# 1_V1.net
KiCad netlist of a schematic drawn in Altium Designer
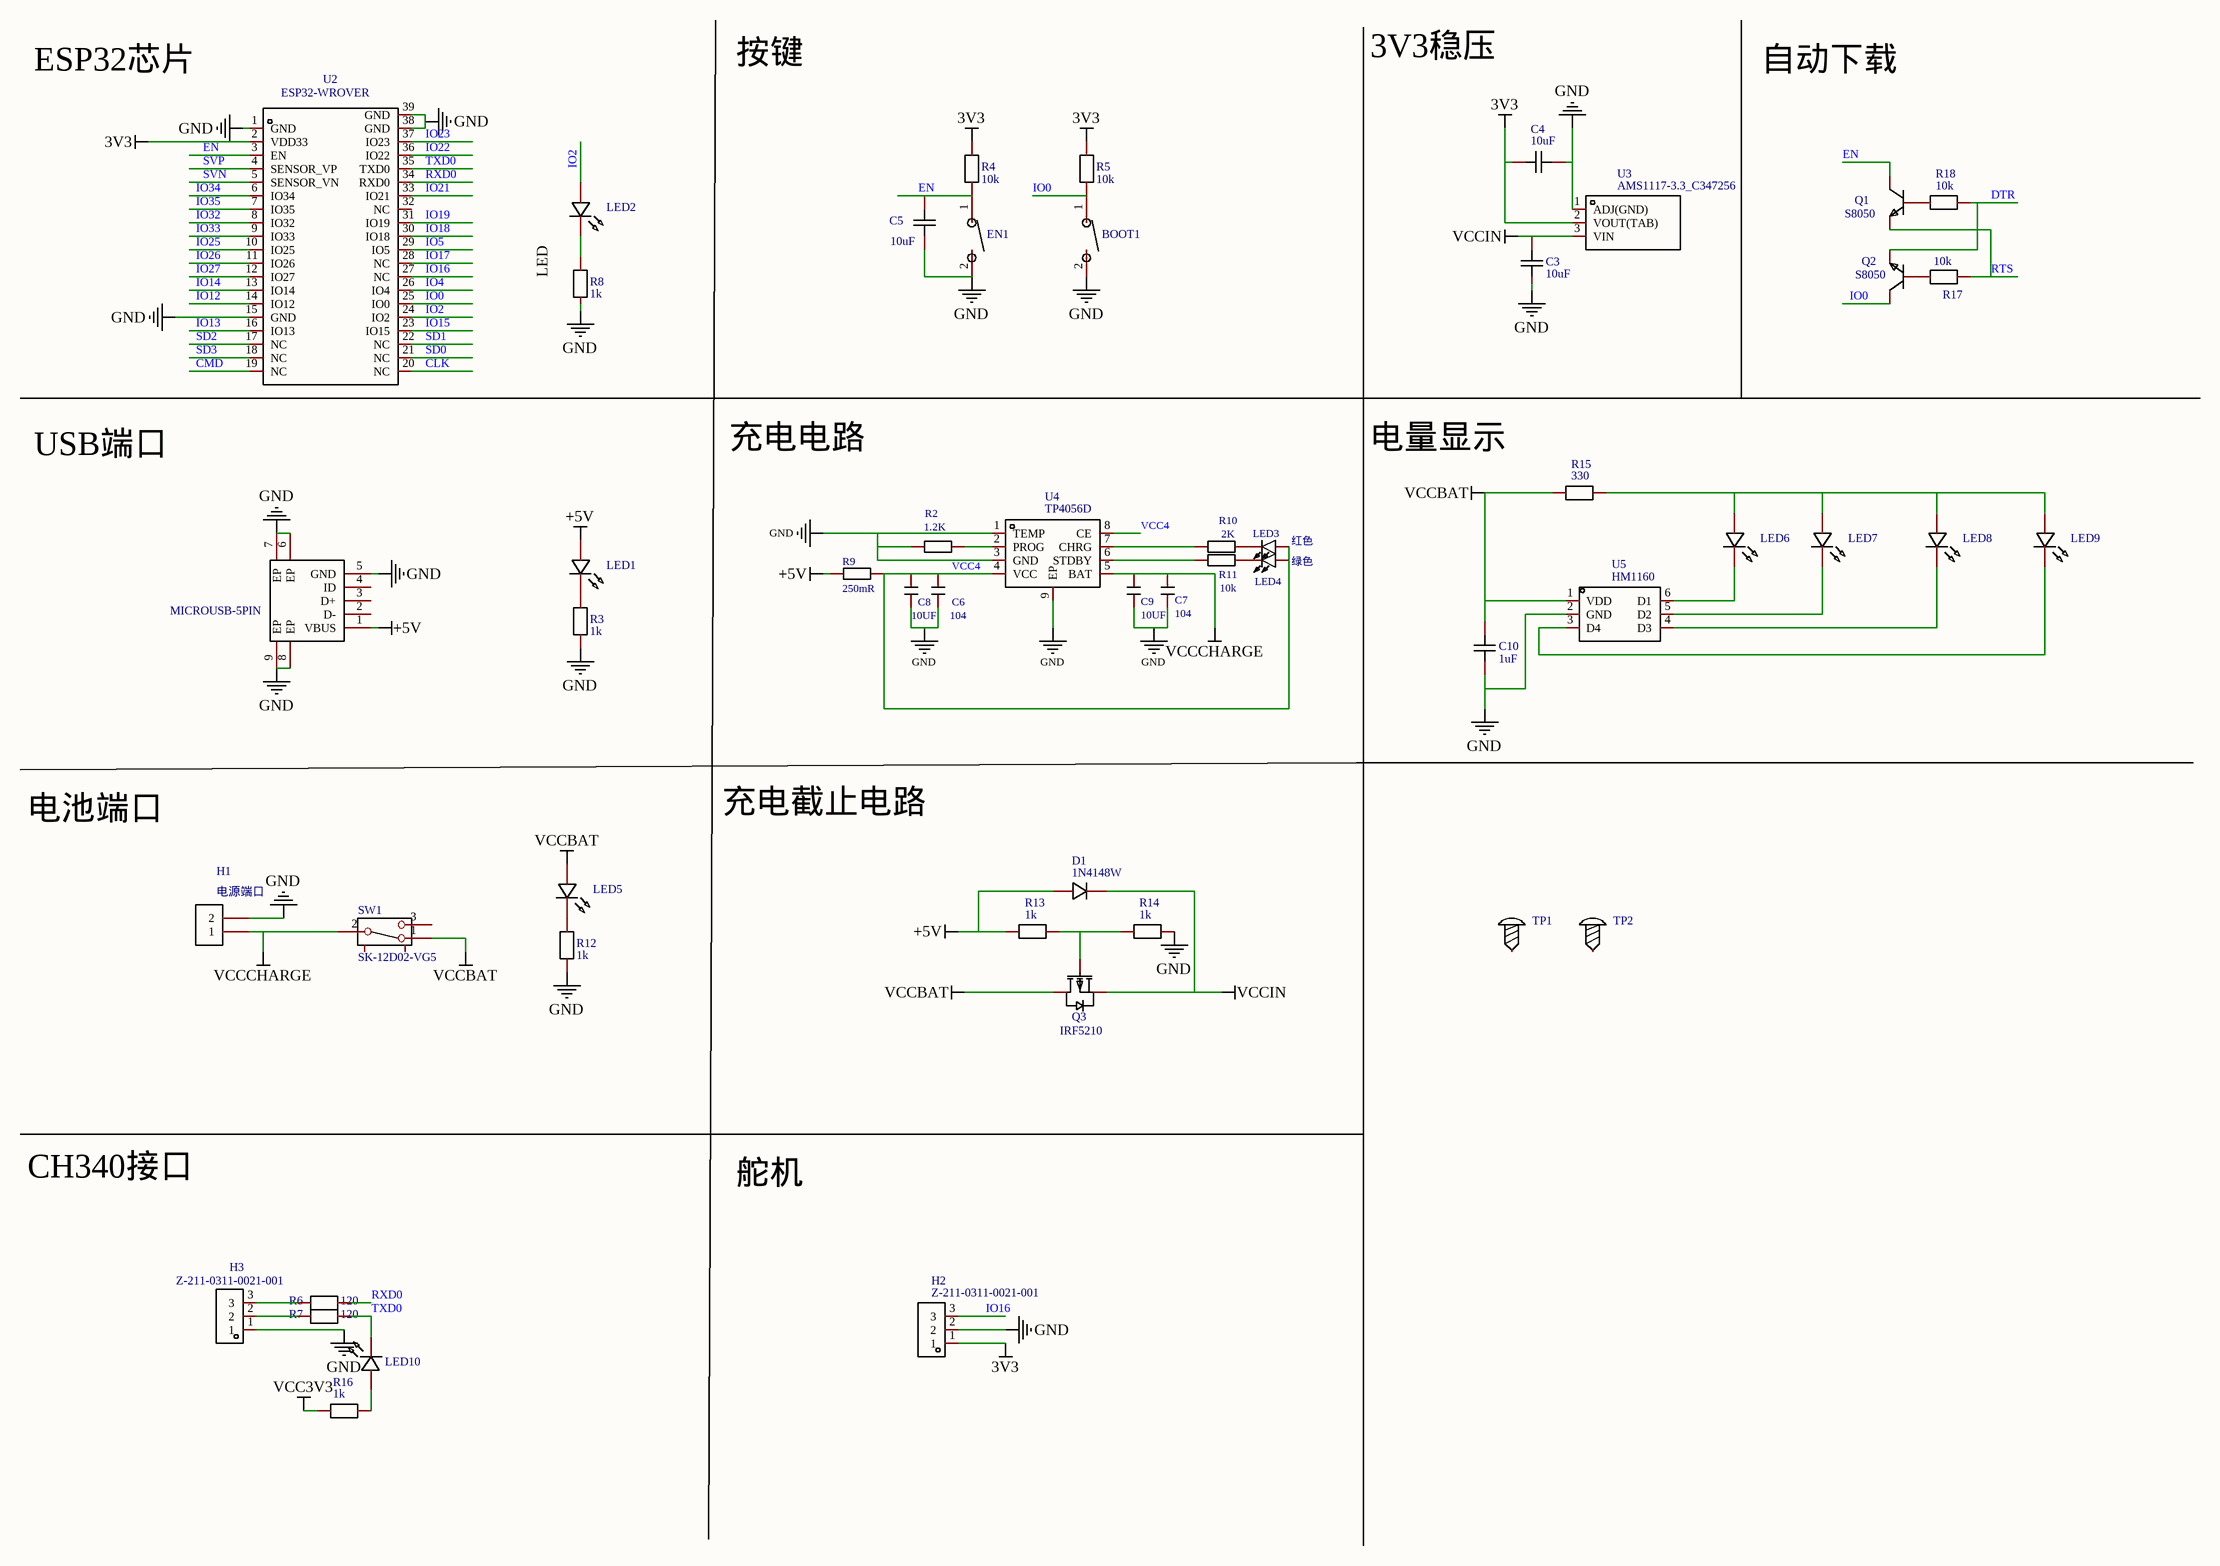
[diagram p0: 1_V1.schdoc]

(export (version "E")
  (design (tool "Eeschema 10.0.6"))
  (components
    (comp (ref "BOOT1")
      (value "TSA343G00D-250J2")
      (description "触点电流:50mA;额定电压(DC):12V;电路结构:单刀单掷;按钮作用方向:顶部触动;致动器样式:圆形按钮;照明颜色:-;开关长度:4mm;开关宽度:3mm;开关高度:2mm;")
      (fields (field (name "MANUFACTURER") "BRIGHT(博瑞泰)"))
      (libsource (lib "altium-import") (part "root_3_TSA343G00D-250J2_"))
    )
    (comp (ref "C3")
      (value "10uF")
      (fields (field (name "NAME") "10uF"))
      (libsource (lib "altium-import") (part "root_3_10uF_"))
    )
    (comp (ref "C4")
      (value "10uF")
      (fields (field (name "NAME") "10uF"))
      (libsource (lib "altium-import") (part "root_0_10uF_"))
    )
    (comp (ref "C5")
      (value "10uF")
      (fields (field (name "NAME") "10uF"))
      (libsource (lib "altium-import") (part "root_1_10uF_"))
    )
    (comp (ref "C6")
      (value "104")
      (fields (field (name "NAME") "104") (field (name "版权归属") "源创客"))
      (libsource (lib "altium-import") (part "root_1_104_"))
    )
    (comp (ref "C7")
      (value "104")
      (fields (field (name "NAME") "104") (field (name "版权归属") "源创客"))
      (libsource (lib "altium-import") (part "root_1_104_"))
    )
    (comp (ref "C8")
      (value "10UF")
      (fields (field (name "NAME") "10UF") (field (name "版权归属") "源创客"))
      (libsource (lib "altium-import") (part "root_1_10UF_"))
    )
    (comp (ref "C9")
      (value "10UF")
      (fields (field (name "NAME") "10UF") (field (name "版权归属") "源创客"))
      (libsource (lib "altium-import") (part "root_1_10UF_"))
    )
    (comp (ref "C10")
      (value "1uF")
      (fields (field (name "NAME") "1uF"))
      (libsource (lib "altium-import") (part "root_1_1uF_"))
    )
    (comp (ref "D1")
      (value "1N4148W")
      (fields (field (name "NAME") "1N4148W") (field (name "MANUFACTURER") "Tak Cheong"))
      (libsource (lib "altium-import") (part "root_0_1N4148W_"))
    )
    (comp (ref "EN1")
      (value "TSA343G00D-250J2")
      (description "触点电流:50mA;额定电压(DC):12V;电路结构:单刀单掷;按钮作用方向:顶部触动;致动器样式:圆形按钮;照明颜色:-;开关长度:4mm;开关宽度:3mm;开关高度:2mm;")
      (fields (field (name "MANUFACTURER") "BRIGHT(博瑞泰)"))
      (libsource (lib "altium-import") (part "root_3_TSA343G00D-250J2_"))
    )
    (comp (ref "H1")
      (value "电源端口")
      (fields
        (field (name "NAME") "电源端口")
        (field (name "MANUFACTURER") "TE Connectivity(美国泰科)")
        (field (name "MANUFACTURER PART") "3-644456-2")
      )
      (libsource (lib "altium-import") (part "root_2_电源端口_"))
    )
    (comp (ref "H2")
      (value "Z-211-0311-0021-001")
      (fields (field (name "NAME") "Z-211-0311-0021-001") (field (name "MANUFACTURER") "Nextron(正凌)"))
      (libsource (lib "altium-import") (part "root_2_Z-211-0311-0021-001_"))
    )
    (comp (ref "H3")
      (value "Z-211-0311-0021-001")
      (fields (field (name "NAME") "Z-211-0311-0021-001") (field (name "MANUFACTURER") "Nextron(正凌)"))
      (libsource (lib "altium-import") (part "root_2_Z-211-0311-0021-001_"))
    )
    (comp (ref "LED1")
      (value "LED-0603_R")
      (fields
        (field (name "MANUFACTURER") "EVERLIGHT(台湾亿光)")
        (field (name "MANUFACTURER PART") "19-217/R6C-AL1M2VY/3T")
      )
      (libsource (lib "altium-import") (part "root_3_LED-0603_R_"))
    )
    (comp (ref "LED2")
      (value "LED-0603_R")
      (fields
        (field (name "MANUFACTURER") "EVERLIGHT(台湾亿光)")
        (field (name "MANUFACTURER PART") "19-217/R6C-AL1M2VY/3T")
      )
      (libsource (lib "altium-import") (part "root_3_LED-0603_R_"))
    )
    (comp (ref "LED3")
      (value "红色")
      (fields (field (name "NAME") "红色") (field (name "版权归属") "源创客"))
      (libsource (lib "altium-import") (part "root_3_红色_"))
    )
    (comp (ref "LED4")
      (value "绿色")
      (fields (field (name "NAME") "绿色") (field (name "版权归属") "源创客"))
      (libsource (lib "altium-import") (part "root_3_绿色_"))
    )
    (comp (ref "LED5")
      (value "LED-0603_R")
      (fields
        (field (name "MANUFACTURER") "EVERLIGHT(台湾亿光)")
        (field (name "MANUFACTURER PART") "19-217/R6C-AL1M2VY/3T")
      )
      (libsource (lib "altium-import") (part "root_3_LED-0603_R_"))
    )
    (comp (ref "LED6")
      (value "LED-0603_R")
      (fields
        (field (name "MANUFACTURER") "EVERLIGHT(台湾亿光)")
        (field (name "MANUFACTURER PART") "19-217/R6C-AL1M2VY/3T")
      )
      (libsource (lib "altium-import") (part "root_3_LED-0603_R_"))
    )
    (comp (ref "LED7")
      (value "LED-0603_R")
      (fields
        (field (name "MANUFACTURER") "EVERLIGHT(台湾亿光)")
        (field (name "MANUFACTURER PART") "19-217/R6C-AL1M2VY/3T")
      )
      (libsource (lib "altium-import") (part "root_3_LED-0603_R_"))
    )
    (comp (ref "LED8")
      (value "LED-0603_R")
      (fields
        (field (name "MANUFACTURER") "EVERLIGHT(台湾亿光)")
        (field (name "MANUFACTURER PART") "19-217/R6C-AL1M2VY/3T")
      )
      (libsource (lib "altium-import") (part "root_3_LED-0603_R_"))
    )
    (comp (ref "LED9")
      (value "LED-0603_R")
      (fields
        (field (name "MANUFACTURER") "EVERLIGHT(台湾亿光)")
        (field (name "MANUFACTURER PART") "19-217/R6C-AL1M2VY/3T")
      )
      (libsource (lib "altium-import") (part "root_3_LED-0603_R_"))
    )
    (comp (ref "LED10")
      (value "LED-0603_R")
      (fields
        (field (name "MANUFACTURER") "EVERLIGHT(台湾亿光)")
        (field (name "MANUFACTURER PART") "19-217/R6C-AL1M2VY/3T")
      )
      (libsource (lib "altium-import") (part "root_1_LED-0603_R_"))
    )
    (comp (ref "NO1")
      (value "MICROUSB-5PIN")
      (fields (field (name "NAME") "MICROUSB-5PIN") (field (name "MANUFACTURER PART") "MicroUSB-5PIN"))
      (libsource (lib "altium-import") (part "root_2_MICROUSB-5PIN_"))
    )
    (comp (ref "Q1")
      (value "S8050")
      (fields (field (name "NAME") "S8050") (field (name "MANUFACTURER") "WPMtek(维攀微)"))
      (libsource (lib "altium-import") (part "root_0_S8050_"))
    )
    (comp (ref "Q2")
      (value "S8050")
      (fields (field (name "NAME") "S8050") (field (name "MANUFACTURER") "WPMtek(维攀微)"))
      (libsource (lib "altium-import") (part "root_2_S8050_"))
    )
    (comp (ref "Q3")
      (value "IRF5210")
      (fields
        (field (name "NAME") "IRF5210")
        (field (name "MANUFACTURER") "IR")
        (field (name "MANUFACTURER PART") "IRF5210STRLPBF")
      )
      (libsource (lib "altium-import") (part "root_3_IRF5210_"))
    )
    (comp (ref "R2")
      (value "1.2K")
      (fields (field (name "NAME") "1.2K") (field (name "版权归属") "源创客"))
      (libsource (lib "altium-import") (part "root_0_1K_"))
    )
    (comp (ref "R3")
      (value "1k")
      (fields (field (name "NAME") "1k"))
      (libsource (lib "altium-import") (part "root_3_1k_"))
    )
    (comp (ref "R4")
      (value "10k")
      (fields (field (name "NAME") "10k"))
      (libsource (lib "altium-import") (part "root_1_10k_"))
    )
    (comp (ref "R5")
      (value "10k")
      (fields (field (name "NAME") "10k"))
      (libsource (lib "altium-import") (part "root_1_10k_"))
    )
    (comp (ref "R6")
      (value "120")
      (fields (field (name "NAME") "120"))
      (libsource (lib "altium-import") (part "root_0_120_"))
    )
    (comp (ref "R7")
      (value "120")
      (fields (field (name "NAME") "120"))
      (libsource (lib "altium-import") (part "root_0_120_"))
    )
    (comp (ref "R8")
      (value "1k")
      (fields (field (name "NAME") "1k"))
      (libsource (lib "altium-import") (part "root_3_1k_"))
    )
    (comp (ref "R9")
      (value "250mR")
      (fields (field (name "NAME") "250mR") (field (name "版权归属") "源创客"))
      (libsource (lib "altium-import") (part "root_0_250mR_"))
    )
    (comp (ref "R10")
      (value "2K")
      (fields (field (name "NAME") "2K") (field (name "版权归属") "源创客"))
      (libsource (lib "altium-import") (part "root_0_2K_"))
    )
    (comp (ref "R11")
      (value "10k")
      (fields (field (name "NAME") "10k") (field (name "版权归属") "源创客"))
      (libsource (lib "") (part "root_0_10k__1"))
    )
    (comp (ref "R12")
      (value "1k")
      (fields (field (name "NAME") "1k"))
      (libsource (lib "altium-import") (part "root_3_1k_"))
    )
    (comp (ref "R13")
      (value "1k")
      (fields (field (name "NAME") "1k"))
      (libsource (lib "altium-import") (part "root_0_1k_"))
    )
    (comp (ref "R14")
      (value "1k")
      (fields (field (name "NAME") "1k"))
      (libsource (lib "altium-import") (part "root_0_1k_"))
    )
    (comp (ref "R15")
      (value "330")
      (fields (field (name "NAME") "330"))
      (libsource (lib "altium-import") (part "root_0_330_"))
    )
    (comp (ref "R16")
      (value "1k")
      (fields (field (name "NAME") "1k"))
      (libsource (lib "altium-import") (part "root_0_1k_"))
    )
    (comp (ref "R17")
      (value "10k")
      (fields (field (name "NAME") "10k"))
      (libsource (lib "altium-import") (part "root_0_10k_"))
    )
    (comp (ref "R18")
      (value "10k")
      (fields (field (name "NAME") "10k"))
      (libsource (lib "altium-import") (part "root_0_10k_"))
    )
    (comp (ref "SW1")
      (value "SK-12D02-VG5")
      (fields (field (name "NAME") "SK-12D02-VG5") (field (name "MANUFACTURER") "韩国韩荣"))
      (libsource (lib "altium-import") (part "root_0_SK-12D02-VG5_C136722_"))
    )
    (comp (ref "TP1") (value "M2螺丝") (libsource (lib "altium-import") (part "root_0_M2螺丝_")))
    (comp (ref "TP2") (value "M2螺丝") (libsource (lib "altium-import") (part "root_0_M2螺丝_")))
    (comp (ref "U2")
      (value "ESP32-WROVER")
      (fields
        (field (name "NAME") "ESP32-WROVER")
        (field (name "MANUFACTURER") "Espressif Systems")
        (field (name "MANUFACTURER PART") "ESP32-WROVER-E(16MB)")
      )
      (libsource (lib "altium-import") (part "root_0_ESP32-WROVER_"))
    )
    (comp (ref "U3")
      (value "AMS1117-3.3_C347256")
      (fields
        (field (name "NAME") "AMS1117-3.3_C347256")
        (field (name "MANUFACTURER") "Youtai Semiconductor Co., Ltd.")
        (field (name "MANUFACTURER PART") "AMS1117-3.3")
      )
      (libsource (lib "altium-import") (part "root_0_AMS1117-3.3_C347256_"))
    )
    (comp (ref "U4")
      (value "TP4056D")
      (fields (field (name "NAME") "TP4056D") (field (name "MANUFACTURER") "拓微集成"))
      (libsource (lib "altium-import") (part "root_0_TP4056D_"))
    )
    (comp (ref "U5")
      (value "HM1160")
      (fields
        (field (name "NAME") "HM1160")
        (field (name "MANUFACTURER") "Shenzhen Chip Hope Micro-Electronics")
        (field (name "MANUFACTURER PART") "LP3772-1")
      )
      (libsource (lib "altium-import") (part "root_0_HM1160_"))
    )
  )
  (nets
    (net (code "1") (name "+5V") (class "Default")
      (node (ref "D1") (pin "2") (pinfunction "2_2") (pintype "passive"))
      (node (ref "LED1") (pin "1") (pinfunction "1_1") (pintype "passive"))
      (node (ref "NO1") (pin "1") (pinfunction "VBUS_1") (pintype "passive"))
      (node (ref "R13") (pin "1") (pinfunction "1_1") (pintype "passive"))
      (node (ref "R9") (pin "1") (pinfunction "1_1") (pintype "passive"))
    )
    (net (code "2") (name "/CLK") (class "Default")
      (node (ref "U2") (pin "20") (pinfunction "NC_20") (pintype "passive"))
    )
    (net (code "3") (name "/CMD") (class "Default")
      (node (ref "U2") (pin "19") (pinfunction "NC_19") (pintype "passive"))
    )
    (net (code "4") (name "/DTR") (class "Default")
      (node (ref "Q2") (pin "2") (pinfunction "E_2") (pintype "passive"))
      (node (ref "R18") (pin "2") (pinfunction "2_2") (pintype "passive"))
    )
    (net (code "5") (name "/EN") (class "Default")
      (node (ref "C5") (pin "2") (pinfunction "2_2") (pintype "passive"))
      (node (ref "EN1") (pin "1") (pinfunction "1_1") (pintype "passive"))
      (node (ref "Q1") (pin "3") (pinfunction "C_3") (pintype "passive"))
      (node (ref "R4") (pin "1") (pinfunction "1_1") (pintype "passive"))
      (node (ref "U2") (pin "3") (pinfunction "EN_3") (pintype "passive"))
    )
    (net (code "6") (name "/IO0") (class "Default")
      (node (ref "BOOT1") (pin "1") (pinfunction "1_1") (pintype "passive"))
      (node (ref "Q2") (pin "3") (pinfunction "C_3") (pintype "passive"))
      (node (ref "R5") (pin "1") (pinfunction "1_1") (pintype "passive"))
      (node (ref "U2") (pin "25") (pinfunction "IO0_25") (pintype "passive"))
    )
    (net (code "7") (name "/IO2") (class "Default")
      (node (ref "LED2") (pin "1") (pinfunction "1_1") (pintype "passive"))
      (node (ref "U2") (pin "24") (pinfunction "IO2_24") (pintype "passive"))
    )
    (net (code "8") (name "/IO4") (class "Default")
      (node (ref "U2") (pin "26") (pinfunction "IO4_26") (pintype "passive"))
    )
    (net (code "9") (name "/IO5") (class "Default")
      (node (ref "U2") (pin "29") (pinfunction "IO5_29") (pintype "passive"))
    )
    (net (code "10") (name "/IO12") (class "Default")
      (node (ref "U2") (pin "14") (pinfunction "IO12_14") (pintype "passive"))
    )
    (net (code "11") (name "/IO13") (class "Default")
      (node (ref "U2") (pin "16") (pinfunction "IO13_16") (pintype "passive"))
    )
    (net (code "12") (name "/IO14") (class "Default")
      (node (ref "U2") (pin "13") (pinfunction "IO14_13") (pintype "passive"))
    )
    (net (code "13") (name "/IO15") (class "Default")
      (node (ref "U2") (pin "23") (pinfunction "IO15_23") (pintype "passive"))
    )
    (net (code "14") (name "/IO16") (class "Default")
      (node (ref "H2") (pin "3") (pinfunction "3_3") (pintype "passive"))
      (node (ref "U2") (pin "27") (pinfunction "NC_27") (pintype "passive"))
    )
    (net (code "15") (name "/IO17") (class "Default")
      (node (ref "U2") (pin "28") (pinfunction "NC_28") (pintype "passive"))
    )
    (net (code "16") (name "/IO18") (class "Default")
      (node (ref "U2") (pin "30") (pinfunction "IO18_30") (pintype "passive"))
    )
    (net (code "17") (name "/IO19") (class "Default")
      (node (ref "U2") (pin "31") (pinfunction "IO19_31") (pintype "passive"))
    )
    (net (code "18") (name "/IO21") (class "Default")
      (node (ref "U2") (pin "33") (pinfunction "IO21_33") (pintype "passive"))
    )
    (net (code "19") (name "/IO22") (class "Default")
      (node (ref "U2") (pin "36") (pinfunction "IO22_36") (pintype "passive"))
    )
    (net (code "20") (name "/IO23") (class "Default")
      (node (ref "U2") (pin "37") (pinfunction "IO23_37") (pintype "passive"))
    )
    (net (code "21") (name "/IO25") (class "Default")
      (node (ref "U2") (pin "10") (pinfunction "IO25_10") (pintype "passive"))
    )
    (net (code "22") (name "/IO26") (class "Default")
      (node (ref "U2") (pin "11") (pinfunction "IO26_11") (pintype "passive"))
    )
    (net (code "23") (name "/IO27") (class "Default")
      (node (ref "U2") (pin "12") (pinfunction "IO27_12") (pintype "passive"))
    )
    (net (code "24") (name "/IO32") (class "Default")
      (node (ref "U2") (pin "8") (pinfunction "IO32_8") (pintype "passive"))
    )
    (net (code "25") (name "/IO33") (class "Default")
      (node (ref "U2") (pin "9") (pinfunction "IO33_9") (pintype "passive"))
    )
    (net (code "26") (name "/IO34") (class "Default")
      (node (ref "U2") (pin "6") (pinfunction "IO34_6") (pintype "passive"))
    )
    (net (code "27") (name "/IO35") (class "Default")
      (node (ref "U2") (pin "7") (pinfunction "IO35_7") (pintype "passive"))
    )
    (net (code "28") (name "/RTS") (class "Default")
      (node (ref "Q1") (pin "2") (pinfunction "E_2") (pintype "passive"))
      (node (ref "R17") (pin "2") (pinfunction "2_2") (pintype "passive"))
    )
    (net (code "29") (name "/RXD0") (class "Default")
      (node (ref "R6") (pin "2") (pinfunction "2_2") (pintype "passive"))
      (node (ref "U2") (pin "34") (pinfunction "RXD0_34") (pintype "passive"))
    )
    (net (code "30") (name "/SD0") (class "Default")
      (node (ref "U2") (pin "21") (pinfunction "NC_21") (pintype "passive"))
    )
    (net (code "31") (name "/SD1") (class "Default")
      (node (ref "U2") (pin "22") (pinfunction "NC_22") (pintype "passive"))
    )
    (net (code "32") (name "/SD2") (class "Default")
      (node (ref "U2") (pin "17") (pinfunction "NC_17") (pintype "passive"))
    )
    (net (code "33") (name "/SD3") (class "Default")
      (node (ref "U2") (pin "18") (pinfunction "NC_18") (pintype "passive"))
    )
    (net (code "34") (name "/SVN") (class "Default")
      (node (ref "U2") (pin "5") (pinfunction "SENSOR_VN_5") (pintype "passive"))
    )
    (net (code "35") (name "/SVP") (class "Default")
      (node (ref "U2") (pin "4") (pinfunction "SENSOR_VP_4") (pintype "passive"))
    )
    (net (code "36") (name "/TXD0") (class "Default")
      (node (ref "LED10") (pin "2") (pinfunction "2_2") (pintype "passive"))
      (node (ref "R7") (pin "2") (pinfunction "2_2") (pintype "passive"))
      (node (ref "U2") (pin "35") (pinfunction "TXD0_35") (pintype "passive"))
    )
    (net (code "37") (name "/VCC4") (class "Default")
      (node (ref "C6") (pin "2") (pinfunction "2_2") (pintype "passive"))
      (node (ref "C8") (pin "2") (pinfunction "2_2") (pintype "passive"))
      (node (ref "LED3") (pin "1") (pinfunction "A_1") (pintype "passive"))
      (node (ref "LED4") (pin "1") (pinfunction "A_1") (pintype "passive"))
      (node (ref "R9") (pin "2") (pinfunction "2_2") (pintype "passive"))
      (node (ref "U4") (pin "4") (pinfunction "VCC_4") (pintype "passive"))
      (node (ref "U4") (pin "8") (pinfunction "CE_8") (pintype "passive"))
    )
    (net (code "38") (name "3V3") (class "Default")
      (node (ref "C4") (pin "1") (pinfunction "1_1") (pintype "passive"))
      (node (ref "H2") (pin "1") (pinfunction "1_1") (pintype "passive"))
      (node (ref "R4") (pin "2") (pinfunction "2_2") (pintype "passive"))
      (node (ref "R5") (pin "2") (pinfunction "2_2") (pintype "passive"))
      (node (ref "U2") (pin "2") (pinfunction "VDD33_2") (pintype "passive"))
      (node (ref "U3") (pin "2") (pinfunction "VOUT(TAB)_2") (pintype "passive"))
    )
    (net (code "39") (name "GND") (class "Default")
      (node (ref "BOOT1") (pin "2") (pinfunction "2_2") (pintype "passive"))
      (node (ref "C10") (pin "1") (pinfunction "1_1") (pintype "passive"))
      (node (ref "C3") (pin "2") (pinfunction "2_2") (pintype "passive"))
      (node (ref "C4") (pin "2") (pinfunction "2_2") (pintype "passive"))
      (node (ref "C5") (pin "1") (pinfunction "1_1") (pintype "passive"))
      (node (ref "C6") (pin "1") (pinfunction "1_1") (pintype "passive"))
      (node (ref "C7") (pin "1") (pinfunction "1_1") (pintype "passive"))
      (node (ref "C8") (pin "1") (pinfunction "1_1") (pintype "passive"))
      (node (ref "C9") (pin "1") (pinfunction "1_1") (pintype "passive"))
      (node (ref "EN1") (pin "2") (pinfunction "2_2") (pintype "passive"))
      (node (ref "H1") (pin "2") (pinfunction "2_2") (pintype "passive"))
      (node (ref "H2") (pin "2") (pinfunction "2_2") (pintype "passive"))
      (node (ref "H3") (pin "1") (pinfunction "1_1") (pintype "passive"))
      (node (ref "NO1") (pin "5") (pinfunction "GND_5") (pintype "passive"))
      (node (ref "NO1") (pin "6") (pinfunction "EP_6") (pintype "passive"))
      (node (ref "NO1") (pin "7") (pinfunction "EP_7") (pintype "passive"))
      (node (ref "NO1") (pin "8") (pinfunction "EP_8") (pintype "passive"))
      (node (ref "NO1") (pin "9") (pinfunction "EP_9") (pintype "passive"))
      (node (ref "R12") (pin "2") (pinfunction "2_2") (pintype "passive"))
      (node (ref "R14") (pin "2") (pinfunction "2_2") (pintype "passive"))
      (node (ref "R2") (pin "1") (pinfunction "1_1") (pintype "passive"))
      (node (ref "R3") (pin "2") (pinfunction "2_2") (pintype "passive"))
      (node (ref "R8") (pin "2") (pinfunction "2_2") (pintype "passive"))
      (node (ref "U2") (pin "1") (pinfunction "GND_1") (pintype "passive"))
      (node (ref "U2") (pin "15") (pinfunction "GND_15") (pintype "passive"))
      (node (ref "U2") (pin "38") (pinfunction "GND_38") (pintype "passive"))
      (node (ref "U2") (pin "39") (pinfunction "GND_39") (pintype "passive"))
      (node (ref "U3") (pin "1") (pinfunction "ADJ(GND)_1") (pintype "passive"))
      (node (ref "U4") (pin "1") (pinfunction "TEMP_1") (pintype "passive"))
      (node (ref "U4") (pin "3") (pinfunction "GND_3") (pintype "passive"))
      (node (ref "U4") (pin "9") (pinfunction "EP_9") (pintype "passive"))
      (node (ref "U5") (pin "2") (pinfunction "GND_2") (pintype "passive"))
    )
    (net (code "40") (name "Net-(H3-Pad2)") (class "Default")
      (node (ref "H3") (pin "2") (pinfunction "2_2") (pintype "passive"))
      (node (ref "R7") (pin "1") (pinfunction "1_1") (pintype "passive"))
    )
    (net (code "41") (name "Net-(H3-Pad3)") (class "Default")
      (node (ref "H3") (pin "3") (pinfunction "3_3") (pintype "passive"))
      (node (ref "R6") (pin "1") (pinfunction "1_1") (pintype "passive"))
    )
    (net (code "42") (name "Net-(LED1-Pad2)") (class "Default")
      (node (ref "LED1") (pin "2") (pinfunction "2_2") (pintype "passive"))
      (node (ref "R3") (pin "1") (pinfunction "1_1") (pintype "passive"))
    )
    (net (code "43") (name "Net-(LED2-Pad2)") (class "Default")
      (node (ref "LED2") (pin "2") (pinfunction "2_2") (pintype "passive"))
      (node (ref "R8") (pin "1") (pinfunction "1_1") (pintype "passive"))
    )
    (net (code "44") (name "Net-(LED3-K)") (class "Default")
      (node (ref "LED3") (pin "2") (pinfunction "K_2") (pintype "passive"))
      (node (ref "R10") (pin "2") (pinfunction "2_2") (pintype "passive"))
    )
    (net (code "45") (name "Net-(LED4-K)") (class "Default")
      (node (ref "LED4") (pin "2") (pinfunction "K_2") (pintype "passive"))
      (node (ref "R11") (pin "2") (pinfunction "2_2") (pintype "passive"))
    )
    (net (code "46") (name "Net-(LED5-Pad2)") (class "Default")
      (node (ref "LED5") (pin "2") (pinfunction "2_2") (pintype "passive"))
      (node (ref "R12") (pin "1") (pinfunction "1_1") (pintype "passive"))
    )
    (net (code "47") (name "Net-(LED6-Pad1)") (class "Default")
      (node (ref "LED6") (pin "1") (pinfunction "1_1") (pintype "passive"))
      (node (ref "LED7") (pin "1") (pinfunction "1_1") (pintype "passive"))
      (node (ref "LED8") (pin "1") (pinfunction "1_1") (pintype "passive"))
      (node (ref "LED9") (pin "1") (pinfunction "1_1") (pintype "passive"))
      (node (ref "R15") (pin "2") (pinfunction "2_2") (pintype "passive"))
    )
    (net (code "48") (name "Net-(LED10-Pad1)") (class "Default")
      (node (ref "LED10") (pin "1") (pinfunction "1_1") (pintype "passive"))
      (node (ref "R16") (pin "2") (pinfunction "2_2") (pintype "passive"))
    )
    (net (code "49") (name "Net-(Q1-B)") (class "Default")
      (node (ref "Q1") (pin "1") (pinfunction "B_1") (pintype "passive"))
      (node (ref "R18") (pin "1") (pinfunction "1_1") (pintype "passive"))
    )
    (net (code "50") (name "Net-(Q2-B)") (class "Default")
      (node (ref "Q2") (pin "1") (pinfunction "B_1") (pintype "passive"))
      (node (ref "R17") (pin "1") (pinfunction "1_1") (pintype "passive"))
    )
    (net (code "51") (name "Net-(Q3-G)") (class "Default")
      (node (ref "Q3") (pin "1") (pinfunction "G_1") (pintype "passive"))
      (node (ref "R13") (pin "2") (pinfunction "2_2") (pintype "passive"))
      (node (ref "R14") (pin "1") (pinfunction "1_1") (pintype "passive"))
    )
    (net (code "52") (name "Net-(U4-CHRG)") (class "Default")
      (node (ref "R10") (pin "1") (pinfunction "1_1") (pintype "passive"))
      (node (ref "U4") (pin "7") (pinfunction "CHRG_7") (pintype "passive"))
    )
    (net (code "53") (name "Net-(U4-PROG)") (class "Default")
      (node (ref "R2") (pin "2") (pinfunction "2_2") (pintype "passive"))
      (node (ref "U4") (pin "2") (pinfunction "PROG_2") (pintype "passive"))
    )
    (net (code "54") (name "Net-(U4-STDBY)") (class "Default")
      (node (ref "R11") (pin "1") (pinfunction "1_1") (pintype "passive"))
      (node (ref "U4") (pin "6") (pinfunction "STDBY_6") (pintype "passive"))
    )
    (net (code "55") (name "Net-(U5-D1)") (class "Default")
      (node (ref "LED6") (pin "2") (pinfunction "2_2") (pintype "passive"))
      (node (ref "U5") (pin "6") (pinfunction "D1_6") (pintype "passive"))
    )
    (net (code "56") (name "Net-(U5-D2)") (class "Default")
      (node (ref "LED7") (pin "2") (pinfunction "2_2") (pintype "passive"))
      (node (ref "U5") (pin "5") (pinfunction "D2_5") (pintype "passive"))
    )
    (net (code "57") (name "Net-(U5-D3)") (class "Default")
      (node (ref "LED8") (pin "2") (pinfunction "2_2") (pintype "passive"))
      (node (ref "U5") (pin "4") (pinfunction "D3_4") (pintype "passive"))
    )
    (net (code "58") (name "Net-(U5-D4)") (class "Default")
      (node (ref "LED9") (pin "2") (pinfunction "2_2") (pintype "passive"))
      (node (ref "U5") (pin "3") (pinfunction "D4_3") (pintype "passive"))
    )
    (net (code "59") (name "VCC3V3") (class "Default")
      (node (ref "R16") (pin "1") (pinfunction "1_1") (pintype "passive"))
    )
    (net (code "60") (name "VCCBAT") (class "Default")
      (node (ref "C10") (pin "2") (pinfunction "2_2") (pintype "passive"))
      (node (ref "LED5") (pin "1") (pinfunction "1_1") (pintype "passive"))
      (node (ref "Q3") (pin "4") (pinfunction "D_4") (pintype "passive"))
      (node (ref "R15") (pin "1") (pinfunction "1_1") (pintype "passive"))
      (node (ref "SW1") (pin "1") (pinfunction "1_1") (pintype "passive"))
      (node (ref "U5") (pin "1") (pinfunction "VDD_1") (pintype "passive"))
    )
    (net (code "61") (name "VCCCHARGE") (class "Default")
      (node (ref "C7") (pin "2") (pinfunction "2_2") (pintype "passive"))
      (node (ref "C9") (pin "2") (pinfunction "2_2") (pintype "passive"))
      (node (ref "H1") (pin "1") (pinfunction "1_1") (pintype "passive"))
      (node (ref "SW1") (pin "2") (pinfunction "2_2") (pintype "passive"))
      (node (ref "U4") (pin "5") (pinfunction "BAT_5") (pintype "passive"))
    )
    (net (code "62") (name "VCCIN") (class "Default")
      (node (ref "C3") (pin "1") (pinfunction "1_1") (pintype "passive"))
      (node (ref "D1") (pin "1") (pinfunction "1_1") (pintype "passive"))
      (node (ref "Q3") (pin "3") (pinfunction "S_3") (pintype "passive"))
      (node (ref "U3") (pin "3") (pinfunction "VIN_3") (pintype "passive"))
    )
    (net (code "63") (name "unconnected-(NO1-D+-Pad3)") (class "Default")
      (node (ref "NO1") (pin "3") (pinfunction "D+_3") (pintype "passive"))
    )
    (net (code "64") (name "unconnected-(NO1-D--Pad2)") (class "Default")
      (node (ref "NO1") (pin "2") (pinfunction "D-_2") (pintype "passive"))
    )
    (net (code "65") (name "unconnected-(NO1-ID-Pad4)") (class "Default")
      (node (ref "NO1") (pin "4") (pinfunction "ID_4") (pintype "passive"))
    )
    (net (code "66") (name "unconnected-(SW1-Pad3)") (class "Default")
      (node (ref "SW1") (pin "3") (pinfunction "3_3") (pintype "passive"))
    )
    (net (code "67") (name "unconnected-(SW1-Pad4)") (class "Default")
      (node (ref "SW1") (pin "4") (pinfunction "4_4") (pintype "passive"))
    )
    (net (code "68") (name "unconnected-(SW1-Pad5)") (class "Default")
      (node (ref "SW1") (pin "5") (pinfunction "5_5") (pintype "passive"))
    )
    (net (code "69") (name "unconnected-(TP1-Pad1)") (class "Default")
      (node (ref "TP1") (pin "1") (pinfunction "1_1") (pintype "passive"))
    )
    (net (code "70") (name "unconnected-(TP2-Pad1)") (class "Default")
      (node (ref "TP2") (pin "1") (pinfunction "1_1") (pintype "passive"))
    )
    (net (code "71") (name "unconnected-(U2-NC-Pad32)") (class "Default")
      (node (ref "U2") (pin "32") (pinfunction "NC_32") (pintype "passive"))
    )
  )
)
